# STM32_Aux.net
KiCad netlist of a schematic drawn in Altium Designer
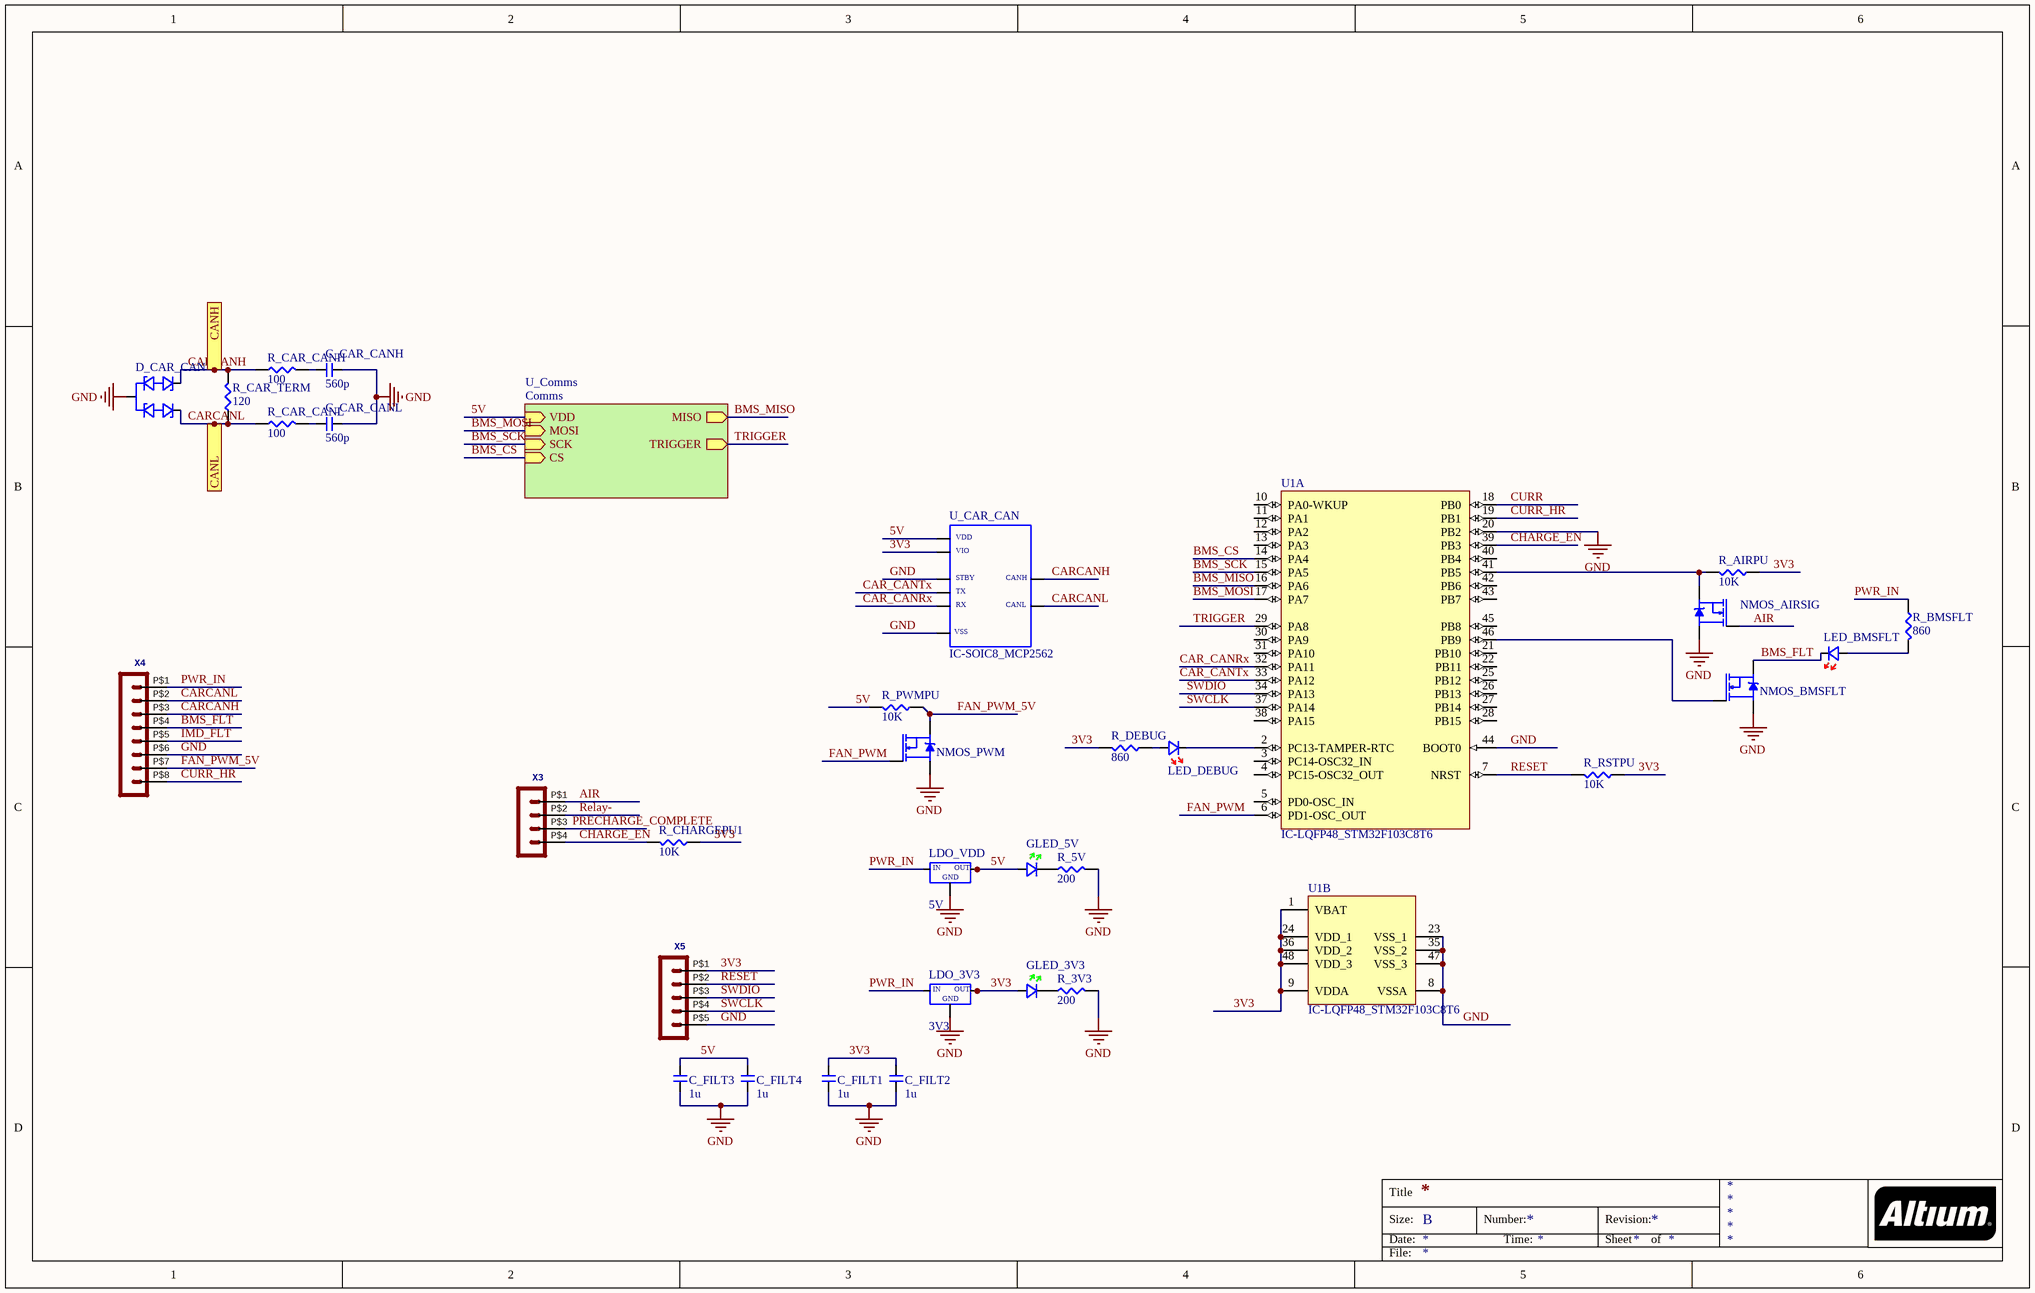
[diagram p0: STM32_Aux.SchDoc]

(export (version "E")
  (design (tool "Eeschema 10.0.6"))
  (components
    (comp (ref "C_CAR_CANH")
      (value "560p")
      (footprint "CAP-0603")
      (libsource (lib "altium-import") (part "root_0_CAP-0603_"))
    )
    (comp (ref "C_CAR_CANL")
      (value "560p")
      (footprint "CAP-0603")
      (libsource (lib "altium-import") (part "root_0_CAP-0603_"))
    )
    (comp (ref "C_FILT1")
      (value "1u")
      (footprint "CAP-0603")
      (libsource (lib "altium-import") (part "root_1_CAP-0603_"))
    )
    (comp (ref "C_FILT2")
      (value "1u")
      (footprint "CAP-0603")
      (libsource (lib "altium-import") (part "root_1_CAP-0603_"))
    )
    (comp (ref "C_FILT3")
      (value "1u")
      (footprint "CAP-0603")
      (libsource (lib "altium-import") (part "root_1_CAP-0603_"))
    )
    (comp (ref "C_FILT4")
      (value "1u")
      (footprint "CAP-0603")
      (libsource (lib "altium-import") (part "root_1_CAP-0603_"))
    )
    (comp (ref "D_CAR_CAN")
      (value "DIODE-SOT23_PESD1CAN")
      (footprint "SOT23")
      (libsource (lib "altium-import") (part "root_0_DIODE-SOT23_PESD1CAN_"))
    )
    (comp (ref "GLED_3V3")
      (value "~")
      (footprint "LEDGREEN-0603")
      (libsource (lib "altium-import") (part "root_0_LEDGREEN-0603_"))
    )
    (comp (ref "GLED_5V")
      (value "~")
      (footprint "LEDGREEN-0603")
      (libsource (lib "altium-import") (part "root_0_LEDGREEN-0603_"))
    )
    (comp (ref "LDO_3V3")
      (value "3V3")
      (footprint "SOT223")
      (libsource (lib "altium-import") (part "root_0_LDO-SOT223_SPX1117_"))
    )
    (comp (ref "LDO_VDD")
      (value "5V")
      (footprint "SOT223")
      (libsource (lib "altium-import") (part "root_0_LDO-SOT223_SPX1117_"))
    )
    (comp (ref "LED_BMSFLT")
      (value "LEDRED-0603")
      (footprint "LEDRED-0603")
      (libsource (lib "altium-import") (part "root_2_LEDRED-0603_"))
    )
    (comp (ref "LED_DEBUG")
      (value "LEDRED-0603")
      (footprint "LEDRED-0603")
      (libsource (lib "altium-import") (part "root_2_mirrored_LEDRED-0603_"))
    )
    (comp (ref "NMOS_AIRSIG")
      (value "NMOS-SOT23")
      (footprint "SOT23")
      (libsource (lib "altium-import") (part "root_0_NMOS-SOT23_"))
    )
    (comp (ref "NMOS_BMSFLT")
      (value "NMOS-SOT23")
      (footprint "SOT23")
      (libsource (lib "altium-import") (part "root_0_mirrored_NMOS-SOT23_"))
    )
    (comp (ref "NMOS_PWM")
      (value "NMOS-SOT23")
      (footprint "SOT23")
      (libsource (lib "altium-import") (part "root_0_mirrored_NMOS-SOT23_"))
    )
    (comp (ref "R_3V3")
      (value "200")
      (footprint "RES-0603")
      (libsource (lib "altium-import") (part "root_0_RES-0603_"))
    )
    (comp (ref "R_5V")
      (value "200")
      (footprint "RES-0603")
      (libsource (lib "altium-import") (part "root_0_RES-0603_"))
    )
    (comp (ref "R_AIRPU")
      (value "10K")
      (footprint "RES-0603")
      (libsource (lib "altium-import") (part "root_2_RES-0603_"))
    )
    (comp (ref "R_BMSFLT")
      (value "860")
      (footprint "RES-0603")
      (libsource (lib "altium-import") (part "root_1_mirrored_RES-0603_"))
    )
    (comp (ref "R_CAR_CANH")
      (value "100")
      (footprint "RES-0603")
      (libsource (lib "altium-import") (part "root_0_RES-0603_"))
    )
    (comp (ref "R_CAR_CANL")
      (value "100")
      (footprint "RES-0603")
      (libsource (lib "altium-import") (part "root_0_RES-0603_"))
    )
    (comp (ref "R_CAR_TERM")
      (value "120")
      (footprint "RES-0603")
      (libsource (lib "altium-import") (part "root_1_RES-0603_"))
    )
    (comp (ref "R_CHARGEPU1")
      (value "10K")
      (footprint "RES-0603")
      (libsource (lib "altium-import") (part "root_2_RES-0603_"))
    )
    (comp (ref "R_DEBUG")
      (value "860")
      (footprint "RES-0603")
      (libsource (lib "altium-import") (part "root_2_RES-0603_"))
    )
    (comp (ref "R_PWMPU")
      (value "10K")
      (footprint "RES-0603")
      (libsource (lib "altium-import") (part "root_2_mirrored_RES-0603_"))
    )
    (comp (ref "R_RSTPU")
      (value "10K")
      (footprint "RES-0603")
      (libsource (lib "altium-import") (part "root_2_RES-0603_"))
    )
    (comp (ref "U1")
      (value "IC-LQFP48_STM32F103C8T6")
      (footprint "STM-LQFP48_M")
      (fields (field (name "PARTNUMBER") "STM32F103C8T6"))
      (libsource (lib "ife19_Elec_Library") (part "IC-LQFP48_STM32F103C8T6"))
    )
    (comp (ref "U_CAR_CAN")
      (value "IC-SOIC8_MCP2562")
      (footprint "SOIC8")
      (libsource (lib "altium-import") (part "root_0_IC-SOIC8_MCP2562_"))
    )
    (comp (ref "X3")
      (value "Molex - Micro-Fit 3.0 Series connector,  3.00mm (0.118\") pitch header, 4 positions.")
      (footprint "43650-0424")
      (libsource (lib "ife19_Elec_Conn_Library") (part "POS4_MF43650-0424"))
    )
    (comp (ref "X4")
      (value "Molex - Micro-Fit 3.0 Series connector,  3.00mm (0.118\") pitch header, 8 positions.")
      (footprint "43650-0824")
      (libsource (lib "MOLEX Micro-Fit") (part "HEADER_POS8_?43650-0824"))
    )
    (comp (ref "X5")
      (value "~")
      (footprint "POS5_254MM_MALE")
      (libsource (lib "altium-import") (part "root_0_mirrored_POS5_254MM_MALE_"))
    )
  )
  (nets
    (net (code "1") (name "/3V3") (class "Default")
      (node (ref "C_FILT1") (pin "2") (pinfunction "2_2") (pintype "passive"))
      (node (ref "C_FILT2") (pin "2") (pinfunction "2_2") (pintype "passive"))
      (node (ref "GLED_3V3") (pin "A") (pinfunction "A_A") (pintype "passive"))
      (node (ref "LDO_3V3") (pin "2") (pinfunction "2_2") (pintype "passive"))
      (node (ref "LDO_3V3") (pin "4") (pinfunction "4_4") (pintype "passive"))
      (node (ref "R_AIRPU") (pin "1") (pinfunction "1_1") (pintype "passive"))
      (node (ref "R_CHARGEPU1") (pin "1") (pinfunction "1_1") (pintype "passive"))
      (node (ref "R_DEBUG") (pin "2") (pinfunction "2_2") (pintype "passive"))
      (node (ref "R_RSTPU") (pin "1") (pinfunction "1_1") (pintype "passive"))
      (node (ref "U1") (pin "1") (pinfunction "VBAT_1") (pintype "power_in"))
      (node (ref "U1") (pin "24") (pinfunction "VDD_1_24") (pintype "power_in"))
      (node (ref "U1") (pin "36") (pinfunction "VDD_2_36") (pintype "power_in"))
      (node (ref "U1") (pin "48") (pinfunction "VDD_3_48") (pintype "power_in"))
      (node (ref "U1") (pin "9") (pinfunction "VDDA_9") (pintype "power_in"))
      (node (ref "U_CAR_CAN") (pin "5") (pinfunction "5_5") (pintype "passive"))
      (node (ref "X5") (pin "P$1") (pinfunction "1_P$1") (pintype "passive"))
    )
    (net (code "2") (name "/5V") (class "Default")
      (node (ref "C_FILT3") (pin "2") (pinfunction "2_2") (pintype "passive"))
      (node (ref "C_FILT4") (pin "2") (pinfunction "2_2") (pintype "passive"))
      (node (ref "GLED_5V") (pin "A") (pinfunction "A_A") (pintype "passive"))
      (node (ref "LDO_VDD") (pin "2") (pinfunction "2_2") (pintype "passive"))
      (node (ref "LDO_VDD") (pin "4") (pinfunction "4_4") (pintype "passive"))
      (node (ref "R_PWMPU") (pin "1") (pinfunction "1_1") (pintype "passive"))
      (node (ref "U_CAR_CAN") (pin "3") (pinfunction "3_3") (pintype "passive"))
    )
    (net (code "3") (name "/AIR") (class "Default")
      (node (ref "NMOS_AIRSIG") (pin "1") (pinfunction "G_1") (pintype "passive"))
      (node (ref "X3") (pin "P$1") (pinfunction "1_P$1") (pintype "passive"))
    )
    (net (code "4") (name "/BMS_CS") (class "Default")
      (node (ref "U1") (pin "14") (pinfunction "PA4_14") (pintype "bidirectional"))
    )
    (net (code "5") (name "/BMS_FLT") (class "Default")
      (node (ref "LED_BMSFLT") (pin "K") (pinfunction "K_K") (pintype "passive"))
      (node (ref "NMOS_BMSFLT") (pin "3") (pinfunction "D_3") (pintype "passive"))
      (node (ref "X4") (pin "P$4") (pinfunction "4_P$4") (pintype "passive"))
    )
    (net (code "6") (name "/BMS_MISO") (class "Default")
      (node (ref "U1") (pin "16") (pinfunction "PA6_16") (pintype "bidirectional"))
    )
    (net (code "7") (name "/BMS_MOSI") (class "Default")
      (node (ref "U1") (pin "17") (pinfunction "PA7_17") (pintype "bidirectional"))
    )
    (net (code "8") (name "/BMS_SCK") (class "Default")
      (node (ref "U1") (pin "15") (pinfunction "PA5_15") (pintype "bidirectional"))
    )
    (net (code "9") (name "/CARCANH") (class "Default")
      (node (ref "D_CAR_CAN") (pin "2") (pinfunction "CAN2_2") (pintype "passive"))
      (node (ref "R_CAR_CANH") (pin "1") (pinfunction "1_1") (pintype "passive"))
      (node (ref "R_CAR_TERM") (pin "2") (pinfunction "2_2") (pintype "passive"))
      (node (ref "U_CAR_CAN") (pin "7") (pinfunction "7_7") (pintype "passive"))
      (node (ref "X4") (pin "P$3") (pinfunction "3_P$3") (pintype "passive"))
    )
    (net (code "10") (name "/CARCANL") (class "Default")
      (node (ref "D_CAR_CAN") (pin "1") (pinfunction "CAN1_1") (pintype "passive"))
      (node (ref "R_CAR_CANL") (pin "1") (pinfunction "1_1") (pintype "passive"))
      (node (ref "R_CAR_TERM") (pin "1") (pinfunction "1_1") (pintype "passive"))
      (node (ref "U_CAR_CAN") (pin "6") (pinfunction "6_6") (pintype "passive"))
      (node (ref "X4") (pin "P$2") (pinfunction "2_P$2") (pintype "passive"))
    )
    (net (code "11") (name "/CAR_CANRx") (class "Default")
      (node (ref "U1") (pin "32") (pinfunction "PA11_32") (pintype "bidirectional"))
      (node (ref "U_CAR_CAN") (pin "4") (pinfunction "4_4") (pintype "passive"))
    )
    (net (code "12") (name "/CAR_CANTx") (class "Default")
      (node (ref "U1") (pin "33") (pinfunction "PA12_33") (pintype "bidirectional"))
      (node (ref "U_CAR_CAN") (pin "1") (pinfunction "1_1") (pintype "passive"))
    )
    (net (code "13") (name "/CHARGE_EN") (class "Default")
      (node (ref "R_CHARGEPU1") (pin "2") (pinfunction "2_2") (pintype "passive"))
      (node (ref "U1") (pin "39") (pinfunction "PB3_39") (pintype "bidirectional"))
      (node (ref "X3") (pin "P$4") (pinfunction "4_P$4") (pintype "passive"))
    )
    (net (code "14") (name "/CURR") (class "Default")
      (node (ref "U1") (pin "18") (pinfunction "PB0_18") (pintype "bidirectional"))
    )
    (net (code "15") (name "/CURR_HR") (class "Default")
      (node (ref "U1") (pin "19") (pinfunction "PB1_19") (pintype "bidirectional"))
      (node (ref "X4") (pin "P$8") (pinfunction "8_P$8") (pintype "passive"))
    )
    (net (code "16") (name "/FAN_PWM") (class "Default")
      (node (ref "NMOS_PWM") (pin "1") (pinfunction "G_1") (pintype "passive"))
      (node (ref "U1") (pin "6") (pinfunction "PD1-OSC_OUT_6") (pintype "bidirectional"))
    )
    (net (code "17") (name "/FAN_PWM_5V") (class "Default")
      (node (ref "NMOS_PWM") (pin "3") (pinfunction "D_3") (pintype "passive"))
      (node (ref "R_PWMPU") (pin "2") (pinfunction "2_2") (pintype "passive"))
      (node (ref "X4") (pin "P$7") (pinfunction "7_P$7") (pintype "passive"))
    )
    (net (code "18") (name "/IMD_FLT") (class "Default")
      (node (ref "X4") (pin "P$5") (pinfunction "5_P$5") (pintype "passive"))
    )
    (net (code "19") (name "/PRECHARGE_COMPLETE") (class "Default")
      (node (ref "X3") (pin "P$3") (pinfunction "3_P$3") (pintype "passive"))
    )
    (net (code "20") (name "/PWR_IN") (class "Default")
      (node (ref "LDO_3V3") (pin "3") (pinfunction "3_3") (pintype "passive"))
      (node (ref "LDO_VDD") (pin "3") (pinfunction "3_3") (pintype "passive"))
      (node (ref "R_BMSFLT") (pin "2") (pinfunction "2_2") (pintype "passive"))
      (node (ref "X4") (pin "P$1") (pinfunction "1_P$1") (pintype "passive"))
    )
    (net (code "21") (name "/RESET") (class "Default")
      (node (ref "R_RSTPU") (pin "2") (pinfunction "2_2") (pintype "passive"))
      (node (ref "U1") (pin "7") (pinfunction "NRST_7") (pintype "bidirectional"))
      (node (ref "X5") (pin "P$2") (pinfunction "2_P$2") (pintype "passive"))
    )
    (net (code "22") (name "/Relay-") (class "Default")
      (node (ref "X3") (pin "P$2") (pinfunction "2_P$2") (pintype "passive"))
    )
    (net (code "23") (name "/SWCLK") (class "Default")
      (node (ref "U1") (pin "37") (pinfunction "PA14_37") (pintype "bidirectional"))
      (node (ref "X5") (pin "P$4") (pinfunction "4_P$4") (pintype "passive"))
    )
    (net (code "24") (name "/SWDIO") (class "Default")
      (node (ref "U1") (pin "34") (pinfunction "PA13_34") (pintype "bidirectional"))
      (node (ref "X5") (pin "P$3") (pinfunction "3_P$3") (pintype "passive"))
    )
    (net (code "25") (name "/TRIGGER") (class "Default")
      (node (ref "U1") (pin "29") (pinfunction "PA8_29") (pintype "bidirectional"))
    )
    (net (code "26") (name "GND") (class "Default")
      (node (ref "C_CAR_CANH") (pin "2") (pinfunction "2_2") (pintype "passive"))
      (node (ref "C_CAR_CANL") (pin "2") (pinfunction "2_2") (pintype "passive"))
      (node (ref "C_FILT1") (pin "1") (pinfunction "1_1") (pintype "passive"))
      (node (ref "C_FILT2") (pin "1") (pinfunction "1_1") (pintype "passive"))
      (node (ref "C_FILT3") (pin "1") (pinfunction "1_1") (pintype "passive"))
      (node (ref "C_FILT4") (pin "1") (pinfunction "1_1") (pintype "passive"))
      (node (ref "D_CAR_CAN") (pin "3") (pinfunction "G_3") (pintype "passive"))
      (node (ref "LDO_3V3") (pin "1") (pinfunction "1_1") (pintype "passive"))
      (node (ref "LDO_VDD") (pin "1") (pinfunction "1_1") (pintype "passive"))
      (node (ref "NMOS_AIRSIG") (pin "2") (pinfunction "S_2") (pintype "passive"))
      (node (ref "NMOS_BMSFLT") (pin "2") (pinfunction "S_2") (pintype "passive"))
      (node (ref "NMOS_PWM") (pin "2") (pinfunction "S_2") (pintype "passive"))
      (node (ref "R_3V3") (pin "2") (pinfunction "2_2") (pintype "passive"))
      (node (ref "R_5V") (pin "2") (pinfunction "2_2") (pintype "passive"))
      (node (ref "U1") (pin "20") (pinfunction "PB2_20") (pintype "bidirectional"))
      (node (ref "U1") (pin "23") (pinfunction "VSS_1_23") (pintype "power_in"))
      (node (ref "U1") (pin "35") (pinfunction "VSS_2_35") (pintype "power_in"))
      (node (ref "U1") (pin "44") (pinfunction "BOOT0_44") (pintype "input"))
      (node (ref "U1") (pin "47") (pinfunction "VSS_3_47") (pintype "power_in"))
      (node (ref "U1") (pin "8") (pinfunction "VSSA_8") (pintype "power_in"))
      (node (ref "U_CAR_CAN") (pin "2") (pinfunction "2_2") (pintype "passive"))
      (node (ref "U_CAR_CAN") (pin "8") (pinfunction "8_8") (pintype "passive"))
      (node (ref "X4") (pin "P$6") (pinfunction "6_P$6") (pintype "passive"))
      (node (ref "X5") (pin "P$5") (pinfunction "5_P$5") (pintype "passive"))
    )
    (net (code "27") (name "Net-(C_CAR_CANH-Pad1)") (class "Default")
      (node (ref "C_CAR_CANH") (pin "1") (pinfunction "1_1") (pintype "passive"))
      (node (ref "R_CAR_CANH") (pin "2") (pinfunction "2_2") (pintype "passive"))
    )
    (net (code "28") (name "Net-(C_CAR_CANL-Pad1)") (class "Default")
      (node (ref "C_CAR_CANL") (pin "1") (pinfunction "1_1") (pintype "passive"))
      (node (ref "R_CAR_CANL") (pin "2") (pinfunction "2_2") (pintype "passive"))
    )
    (net (code "29") (name "Net-(GLED_3V3-PadK)") (class "Default")
      (node (ref "GLED_3V3") (pin "K") (pinfunction "K_K") (pintype "passive"))
      (node (ref "R_3V3") (pin "1") (pinfunction "1_1") (pintype "passive"))
    )
    (net (code "30") (name "Net-(GLED_5V-PadK)") (class "Default")
      (node (ref "GLED_5V") (pin "K") (pinfunction "K_K") (pintype "passive"))
      (node (ref "R_5V") (pin "1") (pinfunction "1_1") (pintype "passive"))
    )
    (net (code "31") (name "Net-(LED_BMSFLT-PadA)") (class "Default")
      (node (ref "LED_BMSFLT") (pin "A") (pinfunction "A_A") (pintype "passive"))
      (node (ref "R_BMSFLT") (pin "1") (pinfunction "1_1") (pintype "passive"))
    )
    (net (code "32") (name "Net-(LED_DEBUG-PadA)") (class "Default")
      (node (ref "LED_DEBUG") (pin "A") (pinfunction "A_A") (pintype "passive"))
      (node (ref "R_DEBUG") (pin "1") (pinfunction "1_1") (pintype "passive"))
    )
    (net (code "33") (name "Net-(NMOS_AIRSIG-D)") (class "Default")
      (node (ref "NMOS_AIRSIG") (pin "3") (pinfunction "D_3") (pintype "passive"))
      (node (ref "R_AIRPU") (pin "2") (pinfunction "2_2") (pintype "passive"))
      (node (ref "U1") (pin "41") (pinfunction "PB5_41") (pintype "bidirectional"))
    )
    (net (code "34") (name "Net-(NMOS_BMSFLT-G)") (class "Default")
      (node (ref "NMOS_BMSFLT") (pin "1") (pinfunction "G_1") (pintype "passive"))
      (node (ref "U1") (pin "46") (pinfunction "PB9_46") (pintype "bidirectional"))
    )
    (net (code "35") (name "Net-(U1A-PC13-TAMPER-RTC)") (class "Default")
      (node (ref "LED_DEBUG") (pin "K") (pinfunction "K_K") (pintype "passive"))
      (node (ref "U1") (pin "2") (pinfunction "PC13-TAMPER-RTC_2") (pintype "bidirectional"))
    )
    (net (code "36") (name "unconnected-(U1A-PA0-WKUP-Pad10)") (class "Default")
      (node (ref "U1") (pin "10") (pinfunction "PA0-WKUP_10") (pintype "bidirectional"))
    )
    (net (code "37") (name "unconnected-(U1A-PA1-Pad11)") (class "Default")
      (node (ref "U1") (pin "11") (pinfunction "PA1_11") (pintype "bidirectional"))
    )
    (net (code "38") (name "unconnected-(U1A-PA2-Pad12)") (class "Default")
      (node (ref "U1") (pin "12") (pinfunction "PA2_12") (pintype "bidirectional"))
    )
    (net (code "39") (name "unconnected-(U1A-PA3-Pad13)") (class "Default")
      (node (ref "U1") (pin "13") (pinfunction "PA3_13") (pintype "bidirectional"))
    )
    (net (code "40") (name "unconnected-(U1A-PA9-Pad30)") (class "Default")
      (node (ref "U1") (pin "30") (pinfunction "PA9_30") (pintype "bidirectional"))
    )
    (net (code "41") (name "unconnected-(U1A-PA10-Pad31)") (class "Default")
      (node (ref "U1") (pin "31") (pinfunction "PA10_31") (pintype "bidirectional"))
    )
    (net (code "42") (name "unconnected-(U1A-PA15-Pad38)") (class "Default")
      (node (ref "U1") (pin "38") (pinfunction "PA15_38") (pintype "bidirectional"))
    )
    (net (code "43") (name "unconnected-(U1A-PB4-Pad40)") (class "Default")
      (node (ref "U1") (pin "40") (pinfunction "PB4_40") (pintype "bidirectional"))
    )
    (net (code "44") (name "unconnected-(U1A-PB6-Pad42)") (class "Default")
      (node (ref "U1") (pin "42") (pinfunction "PB6_42") (pintype "bidirectional"))
    )
    (net (code "45") (name "unconnected-(U1A-PB7-Pad43)") (class "Default")
      (node (ref "U1") (pin "43") (pinfunction "PB7_43") (pintype "bidirectional"))
    )
    (net (code "46") (name "unconnected-(U1A-PB8-Pad45)") (class "Default")
      (node (ref "U1") (pin "45") (pinfunction "PB8_45") (pintype "bidirectional"))
    )
    (net (code "47") (name "unconnected-(U1A-PB10-Pad21)") (class "Default")
      (node (ref "U1") (pin "21") (pinfunction "PB10_21") (pintype "bidirectional"))
    )
    (net (code "48") (name "unconnected-(U1A-PB11-Pad22)") (class "Default")
      (node (ref "U1") (pin "22") (pinfunction "PB11_22") (pintype "bidirectional"))
    )
    (net (code "49") (name "unconnected-(U1A-PB12-Pad25)") (class "Default")
      (node (ref "U1") (pin "25") (pinfunction "PB12_25") (pintype "bidirectional"))
    )
    (net (code "50") (name "unconnected-(U1A-PB13-Pad26)") (class "Default")
      (node (ref "U1") (pin "26") (pinfunction "PB13_26") (pintype "bidirectional"))
    )
    (net (code "51") (name "unconnected-(U1A-PB14-Pad27)") (class "Default")
      (node (ref "U1") (pin "27") (pinfunction "PB14_27") (pintype "bidirectional"))
    )
    (net (code "52") (name "unconnected-(U1A-PB15-Pad28)") (class "Default")
      (node (ref "U1") (pin "28") (pinfunction "PB15_28") (pintype "bidirectional"))
    )
    (net (code "53") (name "unconnected-(U1A-PC14-OSC32_IN-Pad3)") (class "Default")
      (node (ref "U1") (pin "3") (pinfunction "PC14-OSC32_IN_3") (pintype "bidirectional"))
    )
    (net (code "54") (name "unconnected-(U1A-PC15-OSC32_OUT-Pad4)") (class "Default")
      (node (ref "U1") (pin "4") (pinfunction "PC15-OSC32_OUT_4") (pintype "bidirectional"))
    )
    (net (code "55") (name "unconnected-(U1A-PD0-OSC_IN-Pad5)") (class "Default")
      (node (ref "U1") (pin "5") (pinfunction "PD0-OSC_IN_5") (pintype "bidirectional"))
    )
  )
)
